# MAU2.net
KiCad netlist of a schematic drawn in EAGLE
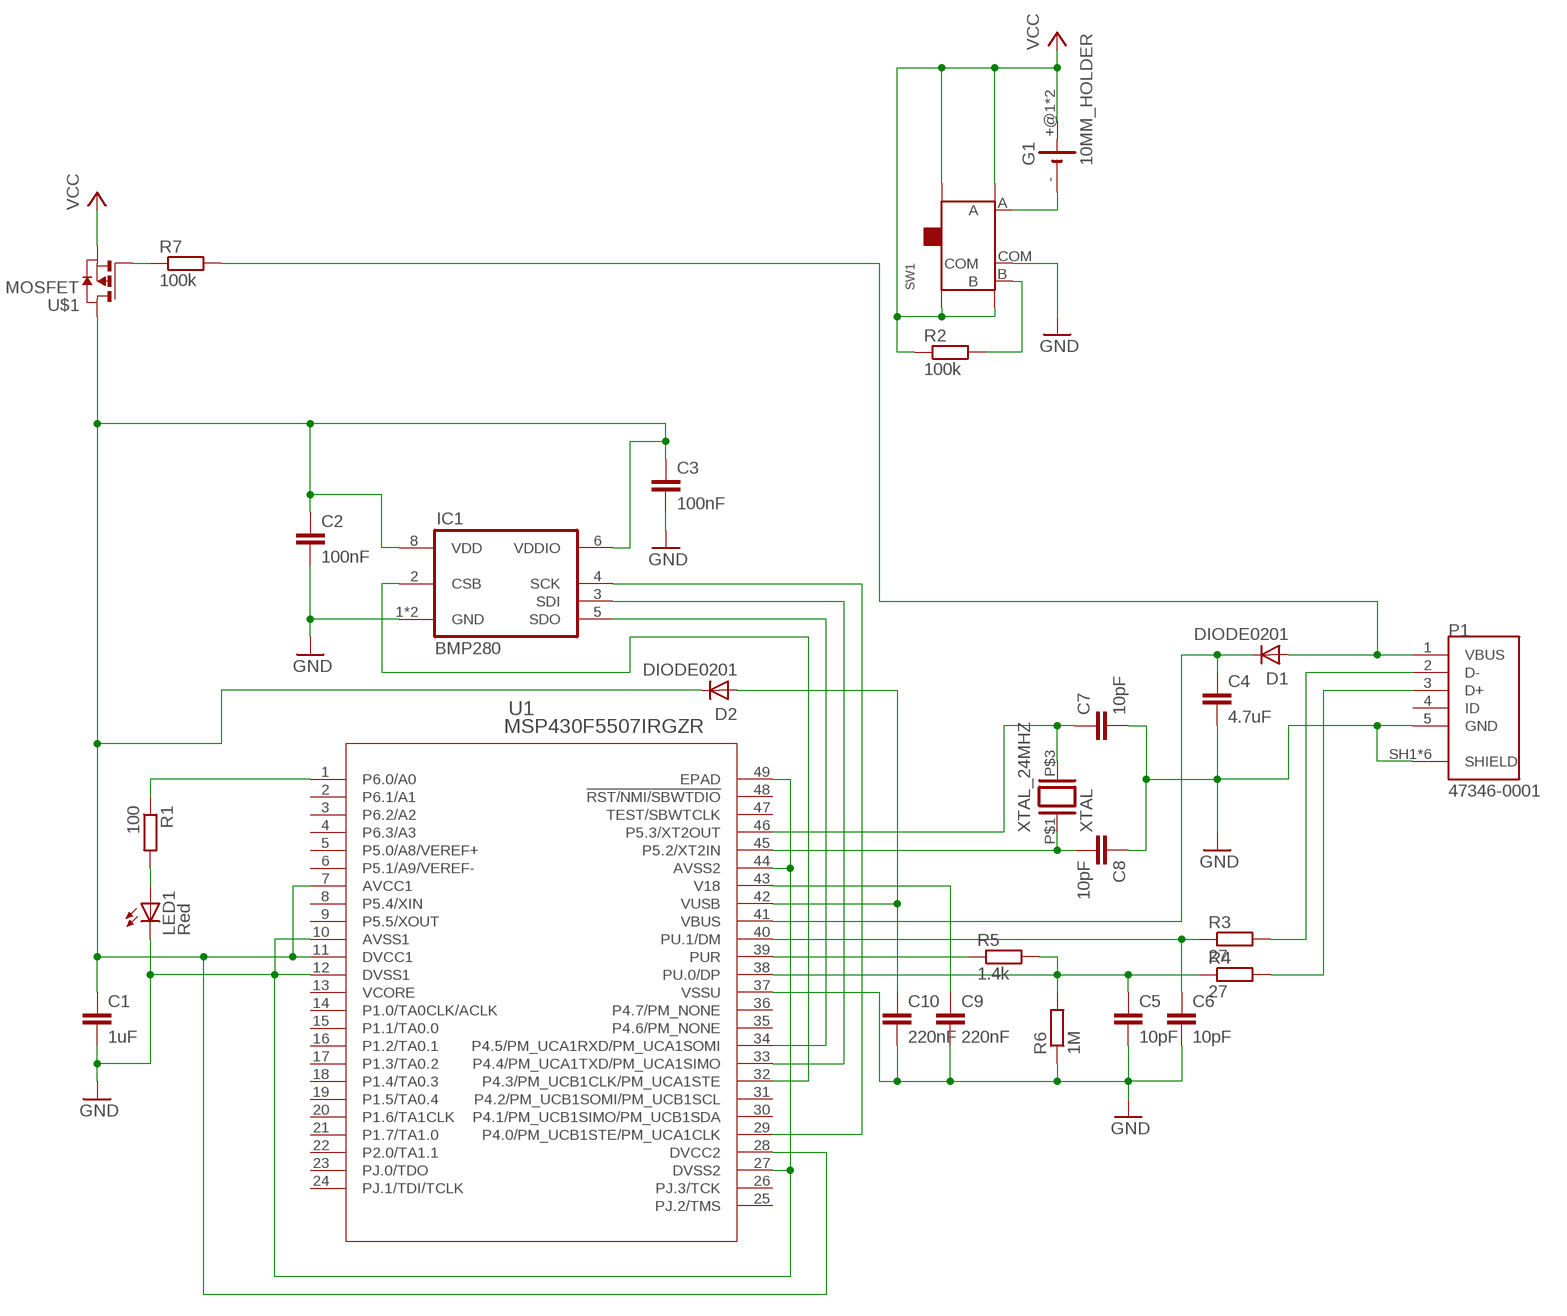
[diagram p0: schematic, sheet 1]

(export (version "E")
  (design (tool "Eeschema 10.0.6"))
  (components
    (comp (ref "C1")
      (value "1uF")
      (footprint "eagle-import:C0201")
      (libsource (lib "eagle-import") (part "C-EUC0201"))
    )
    (comp (ref "C2")
      (value "100nF")
      (footprint "eagle-import:C0201")
      (libsource (lib "eagle-import") (part "C-EUC0201"))
    )
    (comp (ref "C3")
      (value "100nF")
      (footprint "eagle-import:C0201")
      (libsource (lib "eagle-import") (part "C-EUC0201"))
    )
    (comp (ref "C4")
      (value "4.7uF")
      (footprint "eagle-import:C0201")
      (libsource (lib "eagle-import") (part "C-EUC0201"))
    )
    (comp (ref "C5")
      (value "10pF")
      (footprint "eagle-import:C0201")
      (libsource (lib "eagle-import") (part "C-EUC0201"))
    )
    (comp (ref "C6")
      (value "10pF")
      (footprint "eagle-import:C0201")
      (libsource (lib "eagle-import") (part "C-EUC0201"))
    )
    (comp (ref "C7")
      (value "10pF")
      (footprint "eagle-import:C0201")
      (libsource (lib "eagle-import") (part "C-EUC0201"))
    )
    (comp (ref "C8")
      (value "10pF")
      (footprint "eagle-import:C0201")
      (libsource (lib "eagle-import") (part "C-EUC0201"))
    )
    (comp (ref "C9")
      (value "220nF")
      (footprint "eagle-import:C0201")
      (libsource (lib "eagle-import") (part "C-EUC0201"))
    )
    (comp (ref "C10")
      (value "220nF")
      (footprint "eagle-import:C0201")
      (libsource (lib "eagle-import") (part "C-EUC0201"))
    )
    (comp (ref "D1")
      (value "DIODE0201")
      (footprint "eagle-import:0201")
      (libsource (lib "eagle-import") (part "DIODE0201"))
    )
    (comp (ref "D2")
      (value "DIODE0201")
      (footprint "eagle-import:0201")
      (libsource (lib "eagle-import") (part "DIODE0201"))
    )
    (comp (ref "G1")
      (value "10MM_HOLDER")
      (footprint "eagle-import:10MM_HOLDER")
      (libsource (lib "eagle-import") (part "10MM_HOLDER"))
    )
    (comp (ref "IC1")
      (value "BMP280")
      (footprint "eagle-import:BMP280")
      (libsource (lib "eagle-import") (part "BMP280"))
    )
    (comp (ref "LED1")
      (value "Red")
      (footprint "eagle-import:CHIPLED_0603")
      (libsource (lib "eagle-import") (part "LEDCHIPLED_0603"))
    )
    (comp (ref "P1")
      (value "47346-0001")
      (footprint "eagle-import:MOLEX_47346-0001")
      (fields (field (name "MF") "Molex"))
      (libsource (lib "eagle-import") (part "47346-0001"))
    )
    (comp (ref "R1")
      (value "100")
      (footprint "eagle-import:R0201")
      (libsource (lib "eagle-import") (part "R-EU_R0201"))
    )
    (comp (ref "R2")
      (value "100k")
      (footprint "eagle-import:R0201")
      (libsource (lib "eagle-import") (part "R-EU_R0201"))
    )
    (comp (ref "R3")
      (value "27")
      (footprint "eagle-import:R0201")
      (libsource (lib "eagle-import") (part "R-EU_R0201"))
    )
    (comp (ref "R4")
      (value "27")
      (footprint "eagle-import:R0201")
      (libsource (lib "eagle-import") (part "R-EU_R0201"))
    )
    (comp (ref "R5")
      (value "1.4k")
      (footprint "eagle-import:R0201")
      (libsource (lib "eagle-import") (part "R-EU_R0201"))
    )
    (comp (ref "R6")
      (value "1M")
      (footprint "eagle-import:R0201")
      (libsource (lib "eagle-import") (part "R-EU_R0201"))
    )
    (comp (ref "R7")
      (value "100k")
      (footprint "eagle-import:R0201")
      (libsource (lib "eagle-import") (part "R-EU_R0201"))
    )
    (comp (ref "SW1")
      (value "SMD-TOGGLE-SWITCH-ON-ON(3+4P-6.7X2.7MM)SLIDE_LATERAL")
      (footprint "eagle-import:SW7-SMD-6.7X2.6X1.4MM-90D")
      (libsource (lib "eagle-import") (part "SMD-TOGGLE-SWITCH-ON-ON(3+4P-6.7X2.7MM)SLIDE_LATERAL"))
    )
    (comp (ref "U$1")
      (value "MOSFET")
      (footprint "eagle-import:VLM0806")
      (libsource (lib "eagle-import") (part "MOSFET"))
    )
    (comp (ref "U1")
      (value "MSP430F5507IRGZR")
      (footprint "eagle-import:RGZ48_5P15X5P15")
      (libsource (lib "eagle-import") (part "MSP430F5507IRGZR"))
    )
    (comp (ref "XTAL_24MHZ")
      (value "XTAL")
      (footprint "eagle-import:XTAL_SMD_1612")
      (libsource (lib "eagle-import") (part "XTAL"))
    )
  )
  (nets
    (net (code "1") (name "/VCORE") (class "Default")
      (node (ref "U1") (pin "13") (pinfunction "VCORE_13") (pintype "power_in"))
    )
    (net (code "2") (name "GND") (class "Default")
      (node (ref "C1") (pin "2") (pinfunction "2_2") (pintype "passive"))
      (node (ref "C10") (pin "2") (pinfunction "2_2") (pintype "passive"))
      (node (ref "C2") (pin "2") (pinfunction "2_2") (pintype "passive"))
      (node (ref "C3") (pin "2") (pinfunction "2_2") (pintype "passive"))
      (node (ref "C4") (pin "2") (pinfunction "2_2") (pintype "passive"))
      (node (ref "C5") (pin "2") (pinfunction "2_2") (pintype "passive"))
      (node (ref "C6") (pin "2") (pinfunction "2_2") (pintype "passive"))
      (node (ref "C7") (pin "2") (pinfunction "2_2") (pintype "passive"))
      (node (ref "C8") (pin "1") (pinfunction "1_1") (pintype "passive"))
      (node (ref "C9") (pin "2") (pinfunction "2_2") (pintype "passive"))
      (node (ref "IC1") (pin "1") (pinfunction "GND_1") (pintype "power_in"))
      (node (ref "IC1") (pin "7") (pinfunction "GND_7") (pintype "power_in"))
      (node (ref "LED1") (pin "C") (pinfunction "C_C") (pintype "passive"))
      (node (ref "P1") (pin "5") (pinfunction "GND_5") (pintype "power_in"))
      (node (ref "P1") (pin "SH1") (pinfunction "SHIELD_SH1") (pintype "passive"))
      (node (ref "P1") (pin "SH2") (pinfunction "SHIELD_SH2") (pintype "passive"))
      (node (ref "P1") (pin "SH3") (pinfunction "SHIELD_SH3") (pintype "passive"))
      (node (ref "P1") (pin "SH4") (pinfunction "SHIELD_SH4") (pintype "passive"))
      (node (ref "P1") (pin "SH5") (pinfunction "SHIELD_SH5") (pintype "passive"))
      (node (ref "P1") (pin "SH6") (pinfunction "SHIELD_SH6") (pintype "passive"))
      (node (ref "R6") (pin "1") (pinfunction "1_1") (pintype "passive"))
      (node (ref "SW1") (pin "COM") (pinfunction "COM_COM") (pintype "bidirectional"))
      (node (ref "U1") (pin "10") (pinfunction "AVSS1_10") (pintype "power_in"))
      (node (ref "U1") (pin "12") (pinfunction "DVSS1_12") (pintype "power_in"))
      (node (ref "U1") (pin "27") (pinfunction "DVSS2_27") (pintype "power_in"))
      (node (ref "U1") (pin "37") (pinfunction "VSSU_37") (pintype "power_in"))
      (node (ref "U1") (pin "44") (pinfunction "AVSS2_44") (pintype "power_in"))
      (node (ref "U1") (pin "49") (pinfunction "EPAD_49") (pintype "passive"))
    )
    (net (code "3") (name "Net-(D1-A)") (class "Default")
      (node (ref "D1") (pin "2") (pinfunction "A_2") (pintype "passive"))
      (node (ref "P1") (pin "1") (pinfunction "VBUS_1") (pintype "power_in"))
      (node (ref "R7") (pin "2") (pinfunction "2_2") (pintype "passive"))
    )
    (net (code "4") (name "Net-(D1-C)") (class "Default")
      (node (ref "C4") (pin "1") (pinfunction "1_1") (pintype "passive"))
      (node (ref "D1") (pin "1") (pinfunction "C_1") (pintype "passive"))
      (node (ref "U1") (pin "41") (pinfunction "VBUS_41") (pintype "power_in"))
    )
    (net (code "5") (name "Net-(D2-A)") (class "Default")
      (node (ref "C10") (pin "1") (pinfunction "1_1") (pintype "passive"))
      (node (ref "D2") (pin "2") (pinfunction "A_2") (pintype "passive"))
      (node (ref "U1") (pin "42") (pinfunction "VUSB_42") (pintype "power_in"))
    )
    (net (code "6") (name "Net-(D2-C)") (class "Default")
      (node (ref "C1") (pin "1") (pinfunction "1_1") (pintype "passive"))
      (node (ref "C2") (pin "1") (pinfunction "1_1") (pintype "passive"))
      (node (ref "C3") (pin "1") (pinfunction "1_1") (pintype "passive"))
      (node (ref "D2") (pin "1") (pinfunction "C_1") (pintype "passive"))
      (node (ref "IC1") (pin "6") (pinfunction "VDDIO_6") (pintype "power_in"))
      (node (ref "IC1") (pin "8") (pinfunction "VDD_8") (pintype "power_in"))
      (node (ref "U$1") (pin "P$3") (pinfunction "D_P$3") (pintype "passive"))
      (node (ref "U1") (pin "11") (pinfunction "DVCC1_11") (pintype "power_in"))
      (node (ref "U1") (pin "28") (pinfunction "DVCC2_28") (pintype "power_in"))
      (node (ref "U1") (pin "7") (pinfunction "AVCC1_7") (pintype "power_in"))
    )
    (net (code "7") (name "Net-(G1-Pad-)") (class "Default")
      (node (ref "G1") (pin "-") (pinfunction "-_-") (pintype "passive"))
      (node (ref "SW1") (pin "A") (pinfunction "A_A") (pintype "bidirectional"))
    )
    (net (code "8") (name "Net-(IC1-CSB)") (class "Default")
      (node (ref "IC1") (pin "2") (pinfunction "CSB_2") (pintype "input"))
      (node (ref "U1") (pin "32") (pinfunction "P4.3/PM_UCB1CLK/PM_UCA1STE_32") (pintype "bidirectional"))
    )
    (net (code "9") (name "Net-(IC1-SCK)") (class "Default")
      (node (ref "IC1") (pin "4") (pinfunction "SCK_4") (pintype "bidirectional"))
      (node (ref "U1") (pin "29") (pinfunction "P4.0/PM_UCB1STE/PM_UCA1CLK_29") (pintype "bidirectional"))
    )
    (net (code "10") (name "Net-(IC1-SDI)") (class "Default")
      (node (ref "IC1") (pin "3") (pinfunction "SDI_3") (pintype "bidirectional"))
      (node (ref "U1") (pin "33") (pinfunction "P4.4/PM_UCA1TXD/PM_UCA1SIMO_33") (pintype "bidirectional"))
    )
    (net (code "11") (name "Net-(IC1-SDO)") (class "Default")
      (node (ref "IC1") (pin "5") (pinfunction "SDO_5") (pintype "input"))
      (node (ref "U1") (pin "34") (pinfunction "P4.5/PM_UCA1RXD/PM_UCA1SOMI_34") (pintype "bidirectional"))
    )
    (net (code "12") (name "Net-(LED1-PadA)") (class "Default")
      (node (ref "LED1") (pin "A") (pinfunction "A_A") (pintype "passive"))
      (node (ref "R1") (pin "2") (pinfunction "2_2") (pintype "passive"))
    )
    (net (code "13") (name "Net-(P1-D+)") (class "Default")
      (node (ref "P1") (pin "3") (pinfunction "D+_3") (pintype "bidirectional"))
      (node (ref "R4") (pin "2") (pinfunction "2_2") (pintype "passive"))
    )
    (net (code "14") (name "Net-(P1-D-)") (class "Default")
      (node (ref "P1") (pin "2") (pinfunction "D-_2") (pintype "bidirectional"))
      (node (ref "R3") (pin "2") (pinfunction "2_2") (pintype "passive"))
    )
    (net (code "15") (name "Net-(R2-Pad2)") (class "Default")
      (node (ref "R2") (pin "2") (pinfunction "2_2") (pintype "passive"))
      (node (ref "SW1") (pin "B") (pinfunction "B_B") (pintype "bidirectional"))
    )
    (net (code "16") (name "Net-(U$1-G)") (class "Default")
      (node (ref "R7") (pin "1") (pinfunction "1_1") (pintype "passive"))
      (node (ref "U$1") (pin "P$1") (pinfunction "G_P$1") (pintype "passive"))
    )
    (net (code "17") (name "Net-(U1-P5.2{slash}XT2IN)") (class "Default")
      (node (ref "C8") (pin "2") (pinfunction "2_2") (pintype "passive"))
      (node (ref "U1") (pin "45") (pinfunction "P5.2/XT2IN_45") (pintype "bidirectional"))
      (node (ref "XTAL_24MHZ") (pin "P$1") (pinfunction "1_P$1") (pintype "passive"))
    )
    (net (code "18") (name "Net-(U1-P5.3{slash}XT2OUT)") (class "Default")
      (node (ref "C7") (pin "1") (pinfunction "1_1") (pintype "passive"))
      (node (ref "U1") (pin "46") (pinfunction "P5.3/XT2OUT_46") (pintype "bidirectional"))
      (node (ref "XTAL_24MHZ") (pin "P$3") (pinfunction "2_P$3") (pintype "passive"))
    )
    (net (code "19") (name "Net-(U1-P6.0{slash}A0)") (class "Default")
      (node (ref "R1") (pin "1") (pinfunction "1_1") (pintype "passive"))
      (node (ref "U1") (pin "1") (pinfunction "P6.0/A0_1") (pintype "bidirectional"))
    )
    (net (code "20") (name "Net-(U1-PU.0{slash}DP)") (class "Default")
      (node (ref "C5") (pin "1") (pinfunction "1_1") (pintype "passive"))
      (node (ref "R4") (pin "1") (pinfunction "1_1") (pintype "passive"))
      (node (ref "R5") (pin "2") (pinfunction "2_2") (pintype "passive"))
      (node (ref "R6") (pin "2") (pinfunction "2_2") (pintype "passive"))
      (node (ref "U1") (pin "38") (pinfunction "PU.0/DP_38") (pintype "bidirectional"))
    )
    (net (code "21") (name "Net-(U1-PU.1{slash}DM)") (class "Default")
      (node (ref "C6") (pin "1") (pinfunction "1_1") (pintype "passive"))
      (node (ref "R3") (pin "1") (pinfunction "1_1") (pintype "passive"))
      (node (ref "U1") (pin "40") (pinfunction "PU.1/DM_40") (pintype "bidirectional"))
    )
    (net (code "22") (name "Net-(U1-PUR)") (class "Default")
      (node (ref "R5") (pin "1") (pinfunction "1_1") (pintype "passive"))
      (node (ref "U1") (pin "39") (pinfunction "PUR_39") (pintype "bidirectional"))
    )
    (net (code "23") (name "Net-(U1-V18)") (class "Default")
      (node (ref "C9") (pin "1") (pinfunction "1_1") (pintype "passive"))
      (node (ref "U1") (pin "43") (pinfunction "V18_43") (pintype "power_in"))
    )
    (net (code "24") (name "VCC") (class "Default")
      (node (ref "G1") (pin "+@1") (pinfunction "+_+@1") (pintype "passive"))
      (node (ref "G1") (pin "+@2") (pinfunction "+_+@2") (pintype "passive"))
      (node (ref "R2") (pin "1") (pinfunction "1_1") (pintype "passive"))
      (node (ref "SW1") (pin "P1") (pinfunction "SS4_P1") (pintype "bidirectional"))
      (node (ref "SW1") (pin "P2") (pinfunction "SS3_P2") (pintype "bidirectional"))
      (node (ref "SW1") (pin "P3") (pinfunction "SS2_P3") (pintype "bidirectional"))
      (node (ref "SW1") (pin "P4") (pinfunction "SS1_P4") (pintype "bidirectional"))
      (node (ref "U$1") (pin "P$2") (pinfunction "S_P$2") (pintype "passive"))
    )
    (net (code "25") (name "unconnected-(P1-ID-Pad4)") (class "Default")
      (node (ref "P1") (pin "4") (pinfunction "ID_4") (pintype "passive"))
    )
    (net (code "26") (name "unconnected-(U1-P1.0{slash}TA0CLK{slash}ACLK-Pad14)") (class "Default")
      (node (ref "U1") (pin "14") (pinfunction "P1.0/TA0CLK/ACLK_14") (pintype "bidirectional"))
    )
    (net (code "27") (name "unconnected-(U1-P1.1{slash}TA0.0-Pad15)") (class "Default")
      (node (ref "U1") (pin "15") (pinfunction "P1.1/TA0.0_15") (pintype "bidirectional"))
    )
    (net (code "28") (name "unconnected-(U1-P1.2{slash}TA0.1-Pad16)") (class "Default")
      (node (ref "U1") (pin "16") (pinfunction "P1.2/TA0.1_16") (pintype "bidirectional"))
    )
    (net (code "29") (name "unconnected-(U1-P1.3{slash}TA0.2-Pad17)") (class "Default")
      (node (ref "U1") (pin "17") (pinfunction "P1.3/TA0.2_17") (pintype "bidirectional"))
    )
    (net (code "30") (name "unconnected-(U1-P1.4{slash}TA0.3-Pad18)") (class "Default")
      (node (ref "U1") (pin "18") (pinfunction "P1.4/TA0.3_18") (pintype "bidirectional"))
    )
    (net (code "31") (name "unconnected-(U1-P1.5{slash}TA0.4-Pad19)") (class "Default")
      (node (ref "U1") (pin "19") (pinfunction "P1.5/TA0.4_19") (pintype "bidirectional"))
    )
    (net (code "32") (name "unconnected-(U1-P1.6{slash}TA1CLK-Pad20)") (class "Default")
      (node (ref "U1") (pin "20") (pinfunction "P1.6/TA1CLK_20") (pintype "bidirectional"))
    )
    (net (code "33") (name "unconnected-(U1-P1.7{slash}TA1.0-Pad21)") (class "Default")
      (node (ref "U1") (pin "21") (pinfunction "P1.7/TA1.0_21") (pintype "bidirectional"))
    )
    (net (code "34") (name "unconnected-(U1-P2.0{slash}TA1.1-Pad22)") (class "Default")
      (node (ref "U1") (pin "22") (pinfunction "P2.0/TA1.1_22") (pintype "bidirectional"))
    )
    (net (code "35") (name "unconnected-(U1-P4.1{slash}PM_UCB1SIMO{slash}PM_UCB1SDA-Pad30)") (class "Default")
      (node (ref "U1") (pin "30") (pinfunction "P4.1/PM_UCB1SIMO/PM_UCB1SDA_30") (pintype "bidirectional"))
    )
    (net (code "36") (name "unconnected-(U1-P4.2{slash}PM_UCB1SOMI{slash}PM_UCB1SCL-Pad31)") (class "Default")
      (node (ref "U1") (pin "31") (pinfunction "P4.2/PM_UCB1SOMI/PM_UCB1SCL_31") (pintype "bidirectional"))
    )
    (net (code "37") (name "unconnected-(U1-P4.6{slash}PM_NONE-Pad35)") (class "Default")
      (node (ref "U1") (pin "35") (pinfunction "P4.6/PM_NONE_35") (pintype "bidirectional"))
    )
    (net (code "38") (name "unconnected-(U1-P4.7{slash}PM_NONE-Pad36)") (class "Default")
      (node (ref "U1") (pin "36") (pinfunction "P4.7/PM_NONE_36") (pintype "bidirectional"))
    )
    (net (code "39") (name "unconnected-(U1-P5.0{slash}A8{slash}VEREF+-Pad5)") (class "Default")
      (node (ref "U1") (pin "5") (pinfunction "P5.0/A8/VEREF+_5") (pintype "bidirectional"))
    )
    (net (code "40") (name "unconnected-(U1-P5.1{slash}A9{slash}VEREF--Pad6)") (class "Default")
      (node (ref "U1") (pin "6") (pinfunction "P5.1/A9/VEREF-_6") (pintype "bidirectional"))
    )
    (net (code "41") (name "unconnected-(U1-P5.4{slash}XIN-Pad8)") (class "Default")
      (node (ref "U1") (pin "8") (pinfunction "P5.4/XIN_8") (pintype "bidirectional"))
    )
    (net (code "42") (name "unconnected-(U1-P5.5{slash}XOUT-Pad9)") (class "Default")
      (node (ref "U1") (pin "9") (pinfunction "P5.5/XOUT_9") (pintype "bidirectional"))
    )
    (net (code "43") (name "unconnected-(U1-P6.1{slash}A1-Pad2)") (class "Default")
      (node (ref "U1") (pin "2") (pinfunction "P6.1/A1_2") (pintype "bidirectional"))
    )
    (net (code "44") (name "unconnected-(U1-P6.2{slash}A2-Pad3)") (class "Default")
      (node (ref "U1") (pin "3") (pinfunction "P6.2/A2_3") (pintype "bidirectional"))
    )
    (net (code "45") (name "unconnected-(U1-P6.3{slash}A3-Pad4)") (class "Default")
      (node (ref "U1") (pin "4") (pinfunction "P6.3/A3_4") (pintype "bidirectional"))
    )
    (net (code "46") (name "unconnected-(U1-PJ.0{slash}TDO-Pad23)") (class "Default")
      (node (ref "U1") (pin "23") (pinfunction "PJ.0/TDO_23") (pintype "bidirectional"))
    )
    (net (code "47") (name "unconnected-(U1-PJ.1{slash}TDI{slash}TCLK-Pad24)") (class "Default")
      (node (ref "U1") (pin "24") (pinfunction "PJ.1/TDI/TCLK_24") (pintype "bidirectional"))
    )
    (net (code "48") (name "unconnected-(U1-PJ.2{slash}TMS-Pad25)") (class "Default")
      (node (ref "U1") (pin "25") (pinfunction "PJ.2/TMS_25") (pintype "bidirectional"))
    )
    (net (code "49") (name "unconnected-(U1-PJ.3{slash}TCK-Pad26)") (class "Default")
      (node (ref "U1") (pin "26") (pinfunction "PJ.3/TCK_26") (pintype "bidirectional"))
    )
    (net (code "50") (name "unconnected-(U1-TEST{slash}SBWTCLK-Pad47)") (class "Default")
      (node (ref "U1") (pin "47") (pinfunction "TEST/SBWTCLK_47") (pintype "bidirectional"))
    )
    (net (code "51") (name "unconnected-(U1-~{RST{slash}NMI{slash}SBWTDIO}-Pad48)") (class "Default")
      (node (ref "U1") (pin "48") (pinfunction "~{RST/NMI/SBWTDIO}_48") (pintype "bidirectional"))
    )
  )
)
